# Receive_Station_Sch.net
KiCad netlist of a schematic drawn in Altium Designer
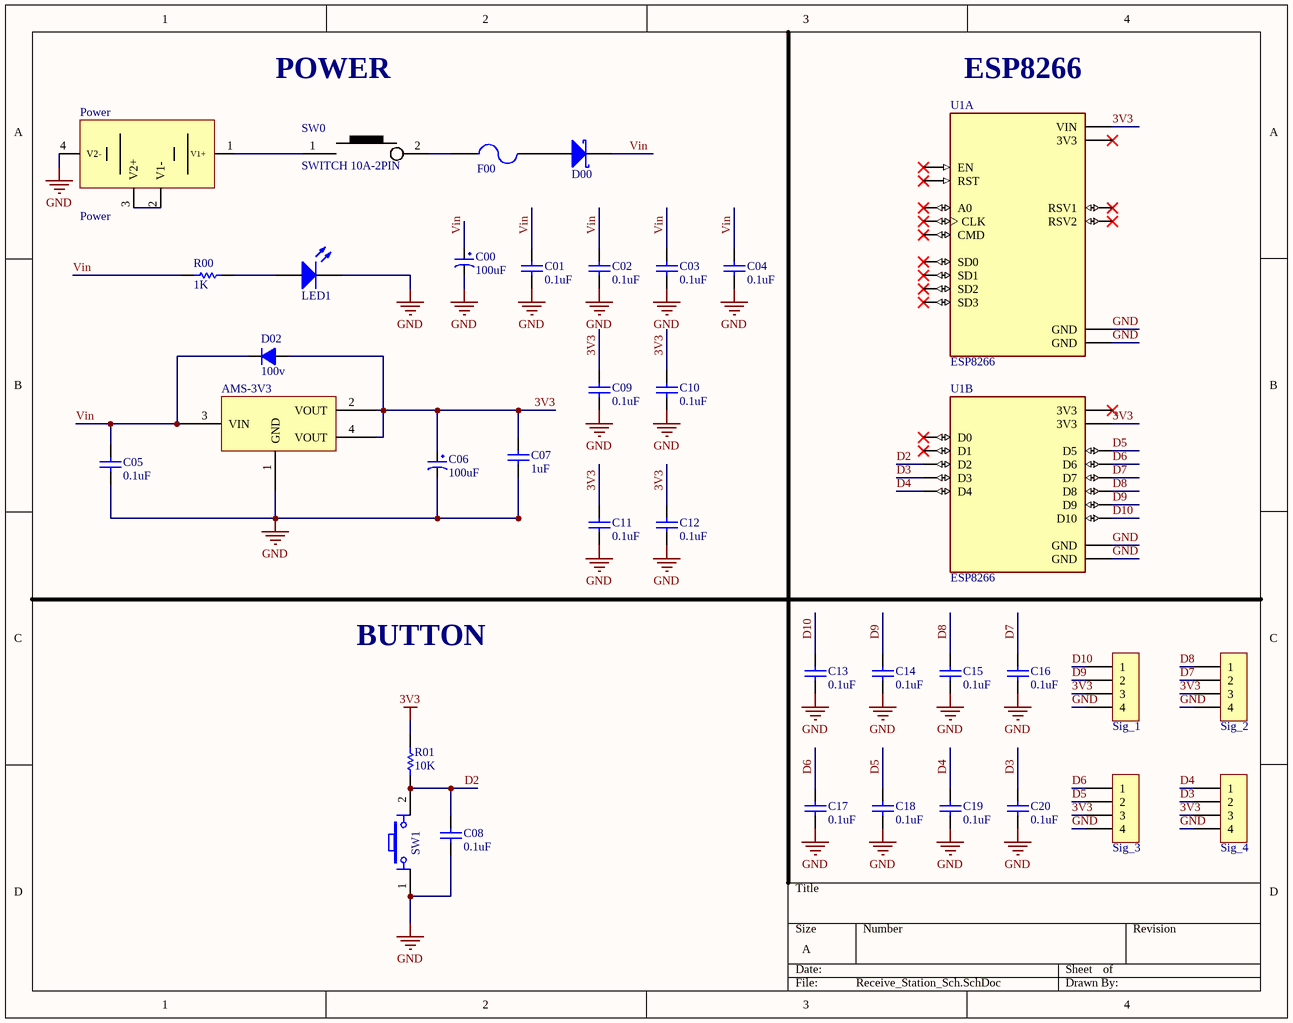
[diagram p0: Receive_Station_Sch.SchDoc]

(export (version "E")
  (design (tool "Eeschema 10.0.6"))
  (components
    (comp (ref "AMS-3V3")
      (value "AMS1117-3.3V")
      (footprint "SOT223")
      (description "Dán")
      (libsource (lib "Altium_Lib_by_KhueNguyenCreator") (part "AMS1117 SMD"))
    )
    (comp (ref "C00")
      (value "100uF")
      (footprint "tu tantalum smd3528")
      (description "Dán")
      (libsource (lib "Altium_Lib_by_KhueNguyenCreator") (part "Tu tantalum 100uF 10V SMD6032"))
    )
    (comp (ref "C01")
      (value "0.1uF")
      (footprint "CAP-SM-0603")
      (description "Capacitor")
      (fields (field (name "Comment") "Cap Non-Pol SMD"))
      (libsource (lib "PIF_Library") (part "Cap Non-Pol SMD"))
    )
    (comp (ref "C02")
      (value "0.1uF")
      (footprint "CAP-SM-0603")
      (description "Capacitor")
      (fields (field (name "Comment") "Cap Non-Pol SMD"))
      (libsource (lib "PIF_Library") (part "Cap Non-Pol SMD"))
    )
    (comp (ref "C03")
      (value "0.1uF")
      (footprint "CAP-SM-0603")
      (description "Capacitor")
      (fields (field (name "Comment") "Cap Non-Pol SMD"))
      (libsource (lib "PIF_Library") (part "Cap Non-Pol SMD"))
    )
    (comp (ref "C04")
      (value "0.1uF")
      (footprint "CAP-SM-0603")
      (description "Capacitor")
      (fields (field (name "Comment") "Cap Non-Pol SMD"))
      (libsource (lib "PIF_Library") (part "Cap Non-Pol SMD"))
    )
    (comp (ref "C05")
      (value "0.1uF")
      (footprint "CAP-SM-0603")
      (description "Capacitor")
      (fields (field (name "Comment") "Cap Non-Pol SMD"))
      (libsource (lib "PIF_Library") (part "Cap Non-Pol SMD"))
    )
    (comp (ref "C06")
      (value "100uF")
      (footprint "tu tantalum smd3528")
      (description "Dán")
      (libsource (lib "Altium_Lib_by_KhueNguyenCreator") (part "Tu tantalum 100uF 10V SMD6032"))
    )
    (comp (ref "C07")
      (value "1uF")
      (footprint "CAP-SM-0603")
      (description "Capacitor")
      (fields (field (name "Comment") "Cap Non-Pol SMD"))
      (libsource (lib "PIF_Library") (part "Cap Non-Pol SMD"))
    )
    (comp (ref "C08")
      (value "0.1uF")
      (footprint "CAP-SM-0603")
      (description "Capacitor")
      (fields (field (name "Comment") "Cap Non-Pol SMD"))
      (libsource (lib "PIF_Library") (part "Cap Non-Pol SMD"))
    )
    (comp (ref "C09")
      (value "0.1uF")
      (footprint "CAP-SM-0603")
      (description "Capacitor")
      (fields (field (name "Comment") "Cap Non-Pol SMD"))
      (libsource (lib "PIF_Library") (part "Cap Non-Pol SMD"))
    )
    (comp (ref "C10")
      (value "0.1uF")
      (footprint "CAP-SM-0603")
      (description "Capacitor")
      (fields (field (name "Comment") "Cap Non-Pol SMD"))
      (libsource (lib "PIF_Library") (part "Cap Non-Pol SMD"))
    )
    (comp (ref "C11")
      (value "0.1uF")
      (footprint "CAP-SM-0603")
      (description "Capacitor")
      (fields (field (name "Comment") "Cap Non-Pol SMD"))
      (libsource (lib "PIF_Library") (part "Cap Non-Pol SMD"))
    )
    (comp (ref "C12")
      (value "0.1uF")
      (footprint "CAP-SM-0603")
      (description "Capacitor")
      (fields (field (name "Comment") "Cap Non-Pol SMD"))
      (libsource (lib "PIF_Library") (part "Cap Non-Pol SMD"))
    )
    (comp (ref "C13")
      (value "0.1uF")
      (footprint "CAP-SM-0603")
      (description "Capacitor")
      (fields (field (name "Comment") "Cap Non-Pol SMD"))
      (libsource (lib "PIF_Library") (part "Cap Non-Pol SMD"))
    )
    (comp (ref "C14")
      (value "0.1uF")
      (footprint "CAP-SM-0603")
      (description "Capacitor")
      (fields (field (name "Comment") "Cap Non-Pol SMD"))
      (libsource (lib "PIF_Library") (part "Cap Non-Pol SMD"))
    )
    (comp (ref "C15")
      (value "0.1uF")
      (footprint "CAP-SM-0603")
      (description "Capacitor")
      (fields (field (name "Comment") "Cap Non-Pol SMD"))
      (libsource (lib "PIF_Library") (part "Cap Non-Pol SMD"))
    )
    (comp (ref "C16")
      (value "0.1uF")
      (footprint "CAP-SM-0603")
      (description "Capacitor")
      (fields (field (name "Comment") "Cap Non-Pol SMD"))
      (libsource (lib "PIF_Library") (part "Cap Non-Pol SMD"))
    )
    (comp (ref "C17")
      (value "0.1uF")
      (footprint "CAP-SM-0603")
      (description "Capacitor")
      (fields (field (name "Comment") "Cap Non-Pol SMD"))
      (libsource (lib "PIF_Library") (part "Cap Non-Pol SMD"))
    )
    (comp (ref "C18")
      (value "0.1uF")
      (footprint "CAP-SM-0603")
      (description "Capacitor")
      (fields (field (name "Comment") "Cap Non-Pol SMD"))
      (libsource (lib "PIF_Library") (part "Cap Non-Pol SMD"))
    )
    (comp (ref "C19")
      (value "0.1uF")
      (footprint "CAP-SM-0603")
      (description "Capacitor")
      (fields (field (name "Comment") "Cap Non-Pol SMD"))
      (libsource (lib "PIF_Library") (part "Cap Non-Pol SMD"))
    )
    (comp (ref "C20")
      (value "0.1uF")
      (footprint "CAP-SM-0603")
      (description "Capacitor")
      (fields (field (name "Comment") "Cap Non-Pol SMD"))
      (libsource (lib "PIF_Library") (part "Cap Non-Pol SMD"))
    )
    (comp (ref "D00")
      (value "D Schottky")
      (footprint "SS34")
      (description "Schottky Diode")
      (fields (field (name "PUBLISHER") "Altium Limited"))
      (libsource (lib "PIF_Library") (part "D Schottky"))
    )
    (comp (ref "D02")
      (value "100v")
      (footprint "DIODE SMA")
      (description "Cắm")
      (libsource (lib "Altium_Lib_by_KhueNguyenCreator") (part "Diode 1N4007"))
    )
    (comp (ref "F00") (value "Fuse") (footprint "FUSE SMD") (libsource (lib "PIF_Library") (part "Fuse")))
    (comp (ref "H1")
      (value "Sig_1")
      (footprint "XH2.54M-4")
      (description "Cắm")
      (libsource (lib "Altium_Lib_by_KhueNguyenCreator") (part "Header 4P 2.54 Duc Thang"))
    )
    (comp (ref "H2")
      (value "Sig_2")
      (footprint "XH2.54M-4")
      (description "Cắm")
      (libsource (lib "Altium_Lib_by_KhueNguyenCreator") (part "Header 4P 2.54 Duc Thang"))
    )
    (comp (ref "H3")
      (value "Sig_3")
      (footprint "XH2.54M-4")
      (description "Cắm")
      (libsource (lib "Altium_Lib_by_KhueNguyenCreator") (part "Header 4P 2.54 Duc Thang"))
    )
    (comp (ref "H4")
      (value "Sig_4")
      (footprint "XH2.54M-4")
      (description "Cắm")
      (libsource (lib "Altium_Lib_by_KhueNguyenCreator") (part "Header 4P 2.54 Duc Thang"))
    )
    (comp (ref "LED1")
      (value "LED SMD")
      (footprint "LED-5MM-WHITE")
      (description "LED")
      (libsource (lib "PIF_Library") (part "LED SMD"))
    )
    (comp (ref "Power") (value "Power") (footprint "18650x2") (libsource (lib "Hold_18650") (part "P?")))
    (comp (ref "R00")
      (value "1K")
      (footprint "RES-SM-0603")
      (description "Resistor")
      (fields (field (name "Comment") "RESISTOR SMD"))
      (libsource (lib "PIF_Library") (part "RESISTOR SMD"))
    )
    (comp (ref "R01")
      (value "10K")
      (footprint "RES-SM-0603")
      (description "Resistor")
      (fields (field (name "Comment") "RESISTOR SMD"))
      (libsource (lib "PIF_Library") (part "RESISTOR SMD"))
    )
    (comp (ref "SW0")
      (value "SWITCH 10A-2PIN")
      (footprint "SW_2ARS_TH")
      (description "Rocker Switch SPST 16A (AC), 10A (DC) 250V Panel Mount, Snap-In")
      (fields
        (field (name "MANUFACTURER") "Würth Elektronik")
        (field (name "MANUFACTURER PART NUMBER") "471005264153")
      )
      (libsource (lib "Altium_Lib_by_KhueNguyenCreator") (part "SW1_RS-471005264153-TH"))
    )
    (comp (ref "SW1")
      (value "Nut Nhan 4 Chan Cam 6x6")
      (footprint "Nut Nhan 4 Chan Cam 6x6")
      (description "Nut Nhan 4 Chan 6x6mm")
      (libsource (lib "Altium_Lib_by_KhueNguyenCreator") (part "Nut Nhan 4 Chan Cam 6x6"))
    )
    (comp (ref "U1")
      (value "ESP8266")
      (footprint "SEEED_113990105")
      (description "- ESP8266 Transceiver; 802.11 b/g (Wi-Fi, WiFi, WLAN) 2.4GHz Evaluation Board")
      (fields (field (name "MP") "113990105") (field (name "MF") "Seeed Technology Co., Ltd"))
      (libsource (lib "113990105") (part "113990105"))
    )
  )
  (nets
    (net (code "1") (name "/D2") (class "Default")
      (node (ref "C08") (pin "2") (pinfunction "2_2") (pintype "passive"))
      (node (ref "R01") (pin "1") (pinfunction "1_1") (pintype "passive"))
      (node (ref "SW1") (pin "2") (pintype "passive"))
      (node (ref "U1") (pin "J2_3") (pinfunction "D2_J2_3") (pintype "bidirectional"))
    )
    (net (code "2") (name "/D3") (class "Default")
      (node (ref "C20") (pin "2") (pinfunction "2_2") (pintype "passive"))
      (node (ref "H4") (pin "2") (pinfunction "2_2") (pintype "passive"))
      (node (ref "U1") (pin "J2_4") (pinfunction "D3_J2_4") (pintype "bidirectional"))
    )
    (net (code "3") (name "/D4") (class "Default")
      (node (ref "C19") (pin "2") (pinfunction "2_2") (pintype "passive"))
      (node (ref "H4") (pin "1") (pinfunction "1_1") (pintype "passive"))
      (node (ref "U1") (pin "J2_5") (pinfunction "D4_J2_5") (pintype "bidirectional"))
    )
    (net (code "4") (name "/D5") (class "Default")
      (node (ref "C18") (pin "2") (pinfunction "2_2") (pintype "passive"))
      (node (ref "H3") (pin "2") (pinfunction "2_2") (pintype "passive"))
      (node (ref "U1") (pin "J2_8") (pinfunction "D5_J2_8") (pintype "bidirectional"))
    )
    (net (code "5") (name "/D6") (class "Default")
      (node (ref "C17") (pin "2") (pinfunction "2_2") (pintype "passive"))
      (node (ref "H3") (pin "1") (pinfunction "1_1") (pintype "passive"))
      (node (ref "U1") (pin "J2_9") (pinfunction "D6_J2_9") (pintype "bidirectional"))
    )
    (net (code "6") (name "/D7") (class "Default")
      (node (ref "C16") (pin "2") (pinfunction "2_2") (pintype "passive"))
      (node (ref "H2") (pin "2") (pinfunction "2_2") (pintype "passive"))
      (node (ref "U1") (pin "J2_10") (pinfunction "D7_J2_10") (pintype "bidirectional"))
    )
    (net (code "7") (name "/D8") (class "Default")
      (node (ref "C15") (pin "2") (pinfunction "2_2") (pintype "passive"))
      (node (ref "H2") (pin "1") (pinfunction "1_1") (pintype "passive"))
      (node (ref "U1") (pin "J2_11") (pinfunction "D8_J2_11") (pintype "bidirectional"))
    )
    (net (code "8") (name "/D9") (class "Default")
      (node (ref "C14") (pin "2") (pinfunction "2_2") (pintype "passive"))
      (node (ref "H1") (pin "2") (pinfunction "2_2") (pintype "passive"))
      (node (ref "U1") (pin "J2_12") (pinfunction "D9_J2_12") (pintype "bidirectional"))
    )
    (net (code "9") (name "/D10") (class "Default")
      (node (ref "C13") (pin "2") (pinfunction "2_2") (pintype "passive"))
      (node (ref "H1") (pin "1") (pinfunction "1_1") (pintype "passive"))
      (node (ref "U1") (pin "J2_13") (pinfunction "D10_J2_13") (pintype "bidirectional"))
    )
    (net (code "10") (name "/Vin") (class "Default")
      (node (ref "AMS-3V3") (pin "3") (pinfunction "VIN_3") (pintype "passive"))
      (node (ref "C00") (pin "1") (pinfunction "1_1") (pintype "passive"))
      (node (ref "C01") (pin "2") (pinfunction "2_2") (pintype "passive"))
      (node (ref "C02") (pin "2") (pinfunction "2_2") (pintype "passive"))
      (node (ref "C03") (pin "2") (pinfunction "2_2") (pintype "passive"))
      (node (ref "C04") (pin "2") (pinfunction "2_2") (pintype "passive"))
      (node (ref "C05") (pin "2") (pinfunction "2_2") (pintype "passive"))
      (node (ref "D00") (pin "2") (pinfunction "K_2") (pintype "passive"))
      (node (ref "D02") (pin "2") (pinfunction "K_2") (pintype "passive"))
      (node (ref "R00") (pin "1") (pinfunction "1_1") (pintype "passive"))
    )
    (net (code "11") (name "3V3") (class "Default")
      (node (ref "AMS-3V3") (pin "2") (pinfunction "VOUT_2") (pintype "passive"))
      (node (ref "AMS-3V3") (pin "4") (pinfunction "VOUT_4") (pintype "passive"))
      (node (ref "C06") (pin "1") (pinfunction "1_1") (pintype "passive"))
      (node (ref "C07") (pin "2") (pinfunction "2_2") (pintype "passive"))
      (node (ref "C09") (pin "2") (pinfunction "2_2") (pintype "passive"))
      (node (ref "C10") (pin "2") (pinfunction "2_2") (pintype "passive"))
      (node (ref "C11") (pin "2") (pinfunction "2_2") (pintype "passive"))
      (node (ref "C12") (pin "2") (pinfunction "2_2") (pintype "passive"))
      (node (ref "D02") (pin "1") (pinfunction "A_1") (pintype "passive"))
      (node (ref "H1") (pin "3") (pinfunction "3_3") (pintype "passive"))
      (node (ref "H2") (pin "3") (pinfunction "3_3") (pintype "passive"))
      (node (ref "H3") (pin "3") (pinfunction "3_3") (pintype "passive"))
      (node (ref "H4") (pin "3") (pinfunction "3_3") (pintype "passive"))
      (node (ref "R01") (pin "2") (pinfunction "2_2") (pintype "passive"))
      (node (ref "U1") (pin "J1_15") (pinfunction "VIN_J1_15") (pintype "power_in"))
      (node (ref "U1") (pin "J2_15") (pinfunction "3V3_J2_15") (pintype "power_in"))
    )
    (net (code "12") (name "GND") (class "Default")
      (node (ref "AMS-3V3") (pin "1") (pinfunction "GND_1") (pintype "passive"))
      (node (ref "C00") (pin "2") (pinfunction "2_2") (pintype "passive"))
      (node (ref "C01") (pin "1") (pinfunction "1_1") (pintype "passive"))
      (node (ref "C02") (pin "1") (pinfunction "1_1") (pintype "passive"))
      (node (ref "C03") (pin "1") (pinfunction "1_1") (pintype "passive"))
      (node (ref "C04") (pin "1") (pinfunction "1_1") (pintype "passive"))
      (node (ref "C05") (pin "1") (pinfunction "1_1") (pintype "passive"))
      (node (ref "C06") (pin "2") (pinfunction "2_2") (pintype "passive"))
      (node (ref "C07") (pin "1") (pinfunction "1_1") (pintype "passive"))
      (node (ref "C08") (pin "1") (pinfunction "1_1") (pintype "passive"))
      (node (ref "C09") (pin "1") (pinfunction "1_1") (pintype "passive"))
      (node (ref "C10") (pin "1") (pinfunction "1_1") (pintype "passive"))
      (node (ref "C11") (pin "1") (pinfunction "1_1") (pintype "passive"))
      (node (ref "C12") (pin "1") (pinfunction "1_1") (pintype "passive"))
      (node (ref "C13") (pin "1") (pinfunction "1_1") (pintype "passive"))
      (node (ref "C14") (pin "1") (pinfunction "1_1") (pintype "passive"))
      (node (ref "C15") (pin "1") (pinfunction "1_1") (pintype "passive"))
      (node (ref "C16") (pin "1") (pinfunction "1_1") (pintype "passive"))
      (node (ref "C17") (pin "1") (pinfunction "1_1") (pintype "passive"))
      (node (ref "C18") (pin "1") (pinfunction "1_1") (pintype "passive"))
      (node (ref "C19") (pin "1") (pinfunction "1_1") (pintype "passive"))
      (node (ref "C20") (pin "1") (pinfunction "1_1") (pintype "passive"))
      (node (ref "H1") (pin "4") (pinfunction "4_4") (pintype "passive"))
      (node (ref "H2") (pin "4") (pinfunction "4_4") (pintype "passive"))
      (node (ref "H3") (pin "4") (pinfunction "4_4") (pintype "passive"))
      (node (ref "H4") (pin "4") (pinfunction "4_4") (pintype "passive"))
      (node (ref "LED1") (pin "2") (pinfunction "K_2") (pintype "passive"))
      (node (ref "Power") (pin "4") (pinfunction "V2-_4") (pintype "passive"))
      (node (ref "SW1") (pin "1") (pintype "passive"))
      (node (ref "U1") (pin "J1_10") (pinfunction "GND_J1_10") (pintype "power_in"))
      (node (ref "U1") (pin "J1_14") (pinfunction "GND_J1_14") (pintype "power_in"))
      (node (ref "U1") (pin "J2_14") (pinfunction "GND_J2_14") (pintype "power_in"))
      (node (ref "U1") (pin "J2_7") (pinfunction "GND_J2_7") (pintype "power_in"))
    )
    (net (code "13") (name "Net-(D00-A)") (class "Default")
      (node (ref "D00") (pin "1") (pinfunction "A_1") (pintype "passive"))
      (node (ref "F00") (pin "2") (pinfunction "2_2") (pintype "passive"))
    )
    (net (code "14") (name "Net-(F00-Pad1)") (class "Default")
      (node (ref "F00") (pin "1") (pinfunction "1_1") (pintype "passive"))
      (node (ref "SW0") (pin "2") (pinfunction "2_2") (pintype "passive"))
    )
    (net (code "15") (name "Net-(LED1-A)") (class "Default")
      (node (ref "LED1") (pin "1") (pinfunction "A_1") (pintype "passive"))
      (node (ref "R00") (pin "2") (pinfunction "2_2") (pintype "passive"))
    )
    (net (code "16") (name "Net-(Power-V1+)") (class "Default")
      (node (ref "Power") (pin "1") (pinfunction "V1+_1") (pintype "passive"))
      (node (ref "SW0") (pin "1") (pinfunction "1_1") (pintype "passive"))
    )
    (net (code "17") (name "Net-(Power-V1-)") (class "Default")
      (node (ref "Power") (pin "2") (pinfunction "V1-_2") (pintype "passive"))
      (node (ref "Power") (pin "3") (pinfunction "V2+_3") (pintype "passive"))
    )
    (net (code "18") (name "unconnected-(U1A-3V3-PadJ1_11)") (class "Default")
      (node (ref "U1") (pin "J1_11") (pinfunction "3V3_J1_11") (pintype "power_in+no_connect"))
    )
    (net (code "19") (name "unconnected-(U1A-A0-PadJ1_1)") (class "Default")
      (node (ref "U1") (pin "J1_1") (pinfunction "A0_J1_1") (pintype "bidirectional+no_connect"))
    )
    (net (code "20") (name "unconnected-(U1A-CLK-PadJ1_9)") (class "Default")
      (node (ref "U1") (pin "J1_9") (pinfunction "CLK_J1_9") (pintype "bidirectional+no_connect"))
    )
    (net (code "21") (name "unconnected-(U1A-CMD-PadJ1_7)") (class "Default")
      (node (ref "U1") (pin "J1_7") (pinfunction "CMD_J1_7") (pintype "bidirectional+no_connect"))
    )
    (net (code "22") (name "unconnected-(U1A-EN-PadJ1_12)") (class "Default")
      (node (ref "U1") (pin "J1_12") (pinfunction "EN_J1_12") (pintype "input+no_connect"))
    )
    (net (code "23") (name "unconnected-(U1A-RST-PadJ1_13)") (class "Default")
      (node (ref "U1") (pin "J1_13") (pinfunction "RST_J1_13") (pintype "input+no_connect"))
    )
    (net (code "24") (name "unconnected-(U1A-RSV1-PadJ1_2)") (class "Default")
      (node (ref "U1") (pin "J1_2") (pinfunction "RSV1_J1_2") (pintype "bidirectional+no_connect"))
    )
    (net (code "25") (name "unconnected-(U1A-RSV2-PadJ1_3)") (class "Default")
      (node (ref "U1") (pin "J1_3") (pinfunction "RSV2_J1_3") (pintype "bidirectional+no_connect"))
    )
    (net (code "26") (name "unconnected-(U1A-SD0-PadJ1_8)") (class "Default")
      (node (ref "U1") (pin "J1_8") (pinfunction "SD0_J1_8") (pintype "bidirectional+no_connect"))
    )
    (net (code "27") (name "unconnected-(U1A-SD1-PadJ1_6)") (class "Default")
      (node (ref "U1") (pin "J1_6") (pinfunction "SD1_J1_6") (pintype "bidirectional+no_connect"))
    )
    (net (code "28") (name "unconnected-(U1A-SD2-PadJ1_5)") (class "Default")
      (node (ref "U1") (pin "J1_5") (pinfunction "SD2_J1_5") (pintype "bidirectional+no_connect"))
    )
    (net (code "29") (name "unconnected-(U1A-SD3-PadJ1_4)") (class "Default")
      (node (ref "U1") (pin "J1_4") (pinfunction "SD3_J1_4") (pintype "bidirectional+no_connect"))
    )
    (net (code "30") (name "unconnected-(U1B-3V3-PadJ2_6)") (class "Default")
      (node (ref "U1") (pin "J2_6") (pinfunction "3V3_J2_6") (pintype "power_in+no_connect"))
    )
    (net (code "31") (name "unconnected-(U1B-D0-PadJ2_1)") (class "Default")
      (node (ref "U1") (pin "J2_1") (pinfunction "D0_J2_1") (pintype "bidirectional+no_connect"))
    )
    (net (code "32") (name "unconnected-(U1B-D1-PadJ2_2)") (class "Default")
      (node (ref "U1") (pin "J2_2") (pinfunction "D1_J2_2") (pintype "bidirectional+no_connect"))
    )
  )
)
